# Wireless_Module_ESP32-H2_V1_0.net
KiCad netlist of a schematic drawn in EAGLE
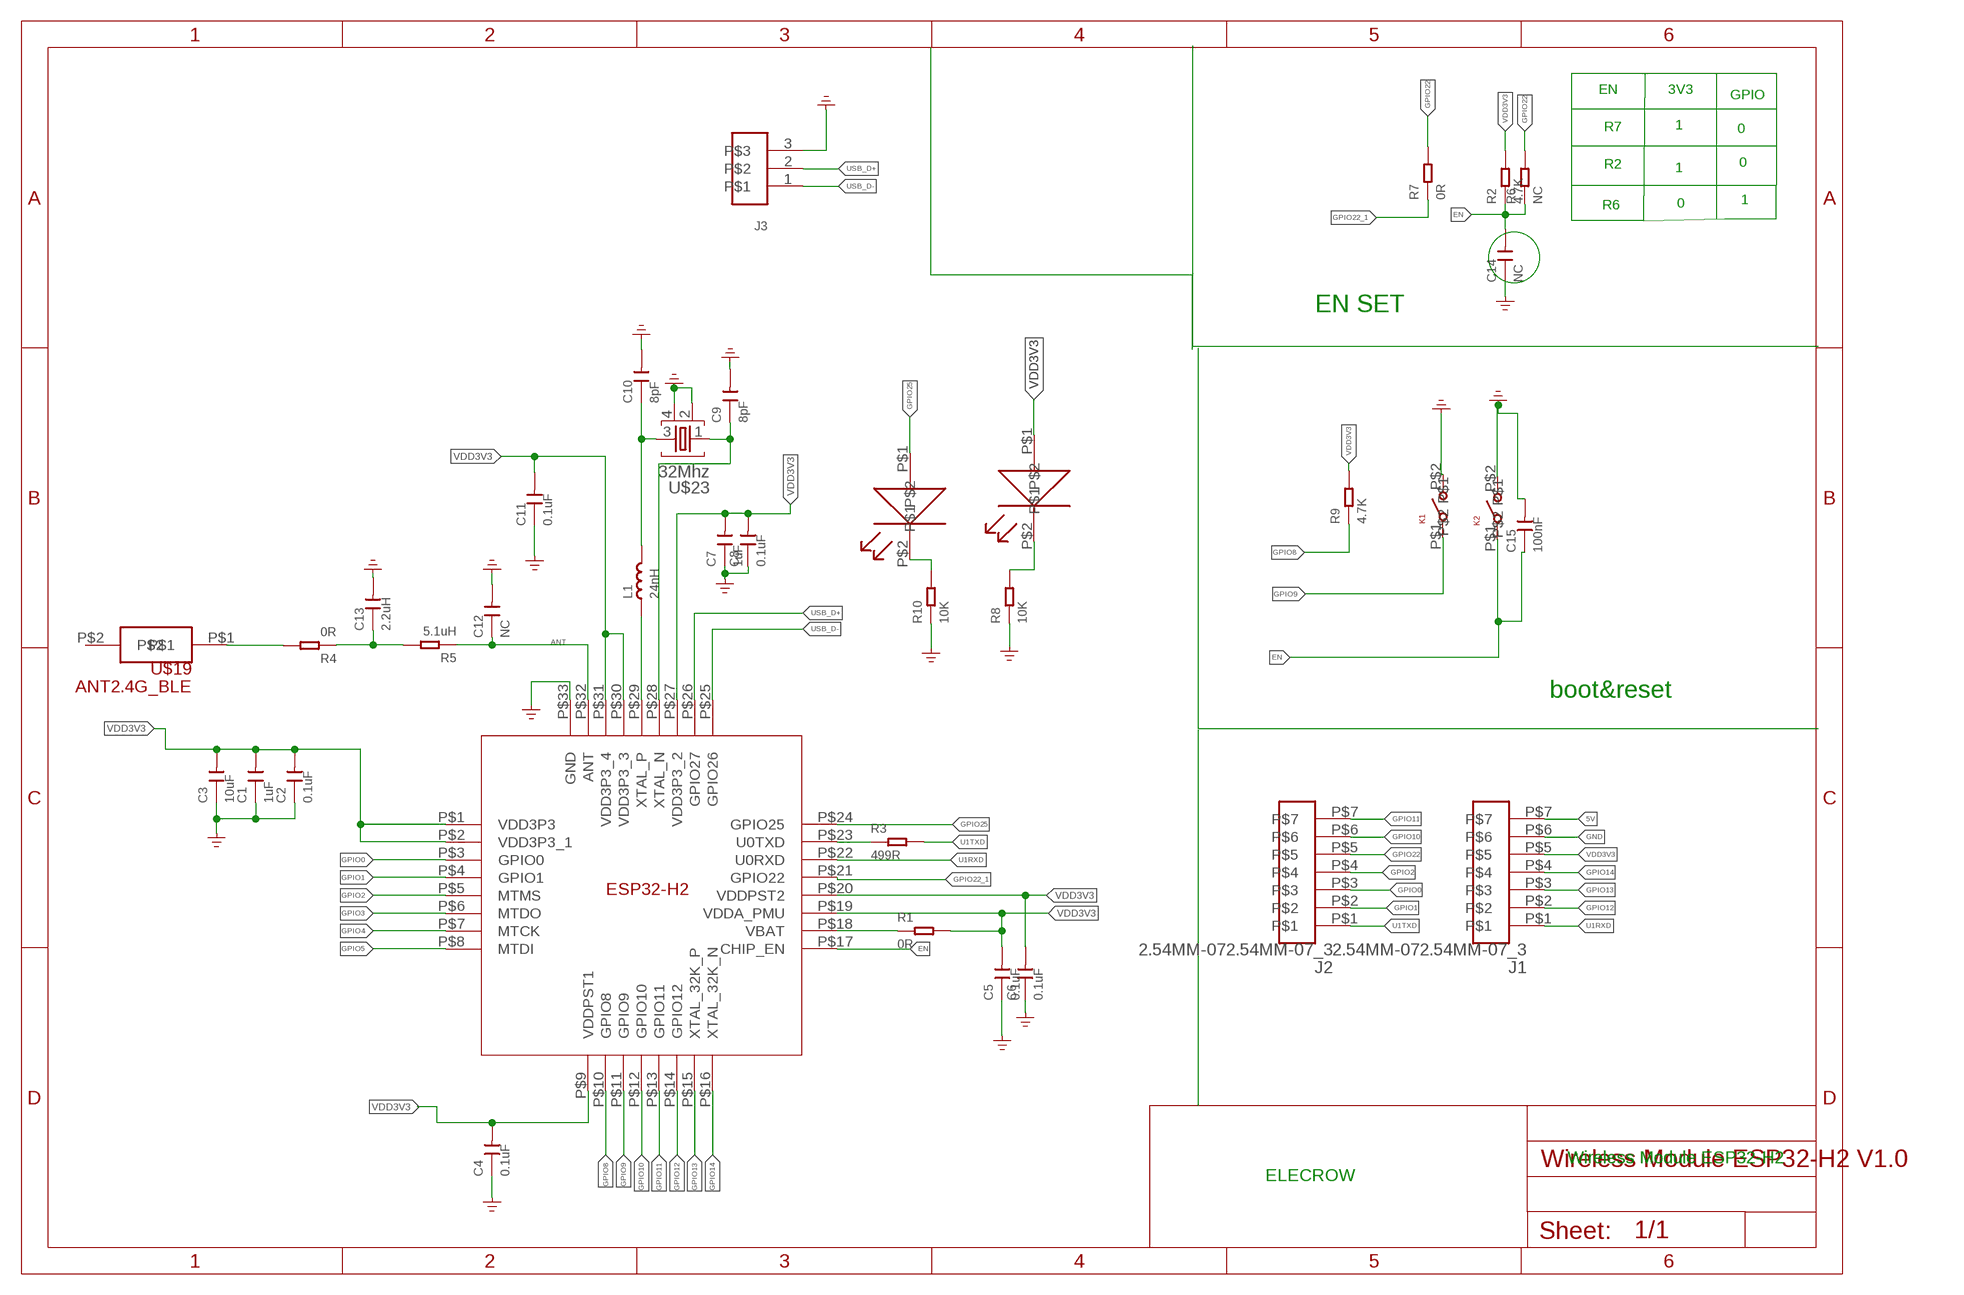
[diagram p0: schematic, sheet 1]

(export (version "E")
  (design (tool "Eeschema 10.0.6"))
  (components
    (comp (ref "C1")
      (value "1uF")
      (footprint "eagle-import:DISCRETE-NEW_C0402")
      (libsource (lib "eagle-import") (part "DISCRETE-NEW_CAP-0402"))
    )
    (comp (ref "C2")
      (value "0.1uF")
      (footprint "eagle-import:DISCRETE-NEW_C0402")
      (libsource (lib "eagle-import") (part "DISCRETE-NEW_CAP-0402"))
    )
    (comp (ref "C3")
      (value "10uF")
      (footprint "eagle-import:DISCRETE-NEW_C0402")
      (libsource (lib "eagle-import") (part "DISCRETE-NEW_CAP-0402"))
    )
    (comp (ref "C4")
      (value "0.1uF")
      (footprint "eagle-import:DISCRETE-NEW_C0402")
      (libsource (lib "eagle-import") (part "DISCRETE-NEW_CAP-0402"))
    )
    (comp (ref "C5")
      (value "0.1uF")
      (footprint "eagle-import:DISCRETE-NEW_C0402")
      (libsource (lib "eagle-import") (part "DISCRETE-NEW_CAP-0402"))
    )
    (comp (ref "C6")
      (value "0.1uF")
      (footprint "eagle-import:DISCRETE-NEW_C0402")
      (libsource (lib "eagle-import") (part "DISCRETE-NEW_CAP-0402"))
    )
    (comp (ref "C7")
      (value "1uF")
      (footprint "eagle-import:DISCRETE-NEW_C0402")
      (libsource (lib "eagle-import") (part "DISCRETE-NEW_CAP-0402"))
    )
    (comp (ref "C8")
      (value "0.1uF")
      (footprint "eagle-import:DISCRETE-NEW_C0402")
      (libsource (lib "eagle-import") (part "DISCRETE-NEW_CAP-0402"))
    )
    (comp (ref "C9")
      (value "8pF")
      (footprint "eagle-import:DISCRETE-NEW_C0402")
      (libsource (lib "eagle-import") (part "DISCRETE-NEW_CAP-0402"))
    )
    (comp (ref "C10")
      (value "8pF")
      (footprint "eagle-import:DISCRETE-NEW_C0402")
      (libsource (lib "eagle-import") (part "DISCRETE-NEW_CAP-0402"))
    )
    (comp (ref "C11")
      (value "0.1uF")
      (footprint "eagle-import:DISCRETE-NEW_C0402")
      (libsource (lib "eagle-import") (part "DISCRETE-NEW_CAP-0402"))
    )
    (comp (ref "C12")
      (value "NC")
      (footprint "eagle-import:DISCRETE-NEW_C0402")
      (libsource (lib "eagle-import") (part "DISCRETE-NEW_CAP-0402"))
    )
    (comp (ref "C13")
      (value "2.2uH")
      (footprint "eagle-import:DISCRETE-NEW_C0402")
      (libsource (lib "eagle-import") (part "DISCRETE-NEW_CAP-0402"))
    )
    (comp (ref "C14")
      (value "NC")
      (footprint "eagle-import:DISCRETE-NEW_C0402")
      (libsource (lib "eagle-import") (part "DISCRETE-NEW_CAP-0402"))
    )
    (comp (ref "C15")
      (value "100nF")
      (footprint "eagle-import:DISCRETE-NEW_C0402")
      (libsource (lib "eagle-import") (part "DISCRETE-NEW_CAP-0402"))
    )
    (comp (ref "J1")
      (value "2.54MM-072.54MM-07_3")
      (footprint "eagle-import:2.54MM-07_3")
      (libsource (lib "eagle-import") (part "2.54MM-072.54MM-07_3"))
    )
    (comp (ref "J2")
      (value "2.54MM-072.54MM-07_3")
      (footprint "eagle-import:2.54MM-07_3")
      (libsource (lib "eagle-import") (part "2.54MM-072.54MM-07_3"))
    )
    (comp (ref "J3")
      (value "1.27MM-3P")
      (footprint "eagle-import:1.27MM-3P")
      (libsource (lib "eagle-import") (part "1.27MM-3P"))
    )
    (comp (ref "K1")
      (value "KEY_SMD")
      (footprint "eagle-import:KEY_3_2.5")
      (libsource (lib "eagle-import") (part "KEY_SMD"))
    )
    (comp (ref "K2")
      (value "KEY_SMD")
      (footprint "eagle-import:KEY_3_2.5")
      (libsource (lib "eagle-import") (part "KEY_SMD"))
    )
    (comp (ref "L1")
      (value "24nH")
      (footprint "eagle-import:DISCRETE-NEW_L0402")
      (libsource (lib "eagle-import") (part "DISCRETE-NEW_INDUCTOR/FERRITE-BEAD0402"))
    )
    (comp (ref "LED1")
      (value "LED_SMT")
      (footprint "eagle-import:LED_0402")
      (libsource (lib "eagle-import") (part "LED_SMT"))
    )
    (comp (ref "LED2")
      (value "LED_SMT")
      (footprint "eagle-import:LED_0402")
      (libsource (lib "eagle-import") (part "LED_SMT"))
    )
    (comp (ref "R1")
      (value "0R")
      (footprint "eagle-import:DISCRETE-NEW_R0402")
      (libsource (lib "eagle-import") (part "DISCRETE-NEW_RES-0402"))
    )
    (comp (ref "R2")
      (value "4.7K")
      (footprint "eagle-import:DISCRETE-NEW_R0402")
      (libsource (lib "eagle-import") (part "DISCRETE-NEW_RES-0402"))
    )
    (comp (ref "R3")
      (value "499R")
      (footprint "eagle-import:DISCRETE-NEW_R0402")
      (libsource (lib "eagle-import") (part "DISCRETE-NEW_RES-0402"))
    )
    (comp (ref "R4")
      (value "0R")
      (footprint "eagle-import:DISCRETE-NEW_R0402")
      (libsource (lib "eagle-import") (part "DISCRETE-NEW_RES-0402"))
    )
    (comp (ref "R5")
      (value "5.1uH")
      (footprint "eagle-import:DISCRETE-NEW_R0402")
      (libsource (lib "eagle-import") (part "DISCRETE-NEW_RES-0402"))
    )
    (comp (ref "R6")
      (value "NC")
      (footprint "eagle-import:DISCRETE-NEW_R0402")
      (libsource (lib "eagle-import") (part "DISCRETE-NEW_RES-0402"))
    )
    (comp (ref "R7")
      (value "0R")
      (footprint "eagle-import:DISCRETE-NEW_R0402")
      (libsource (lib "eagle-import") (part "DISCRETE-NEW_RES-0402"))
    )
    (comp (ref "R8")
      (value "10K")
      (footprint "eagle-import:DISCRETE-NEW_R0402")
      (libsource (lib "eagle-import") (part "DISCRETE-NEW_RES-0402"))
    )
    (comp (ref "R9")
      (value "4.7K")
      (footprint "eagle-import:DISCRETE-NEW_R0402")
      (libsource (lib "eagle-import") (part "DISCRETE-NEW_RES-0402"))
    )
    (comp (ref "R10")
      (value "10K")
      (footprint "eagle-import:DISCRETE-NEW_R0402")
      (libsource (lib "eagle-import") (part "DISCRETE-NEW_RES-0402"))
    )
    (comp (ref "U$1")
      (value "ESP32-H2")
      (footprint "eagle-import:ESP32-H2")
      (libsource (lib "eagle-import") (part "ESP32-H2"))
    )
    (comp (ref "U$19")
      (value "ANT2.4G_BLE")
      (footprint "eagle-import:2.4G_BLE")
      (libsource (lib "eagle-import") (part "ANT2.4G_BLE"))
    )
    (comp (ref "U$23")
      (value "32Mhz")
      (footprint "eagle-import:NORDIC_NRF_BT-XTAL_2016_N")
      (libsource (lib "eagle-import") (part "NORDIC_NRF_XTAL_32MHZ"))
    )
  )
  (nets
    (net (code "1") (name "/ANT") (class "Default")
      (node (ref "C12") (pin "1") (pinfunction "1_1") (pintype "passive"))
      (node (ref "R5") (pin "1") (pinfunction "1_1") (pintype "passive"))
      (node (ref "U$1") (pin "P$32") (pinfunction "ANT_P$32") (pintype "bidirectional"))
    )
    (net (code "2") (name "5V") (class "Default")
      (node (ref "J1") (pin "P$7") (pinfunction "P$7_P$7") (pintype "bidirectional"))
    )
    (net (code "3") (name "EN") (class "Default")
      (node (ref "C14") (pin "2") (pinfunction "2_2") (pintype "passive"))
      (node (ref "C15") (pin "1") (pinfunction "1_1") (pintype "passive"))
      (node (ref "K2") (pin "P$1") (pinfunction "P$1_P$1") (pintype "bidirectional"))
      (node (ref "R2") (pin "1") (pinfunction "1_1") (pintype "passive"))
      (node (ref "R6") (pin "1") (pinfunction "1_1") (pintype "passive"))
      (node (ref "U$1") (pin "P$17") (pinfunction "CHIP_EN_P$17") (pintype "bidirectional"))
    )
    (net (code "4") (name "GND") (class "Default")
      (node (ref "C1") (pin "1") (pinfunction "1_1") (pintype "passive"))
      (node (ref "C10") (pin "2") (pinfunction "2_2") (pintype "passive"))
      (node (ref "C11") (pin "1") (pinfunction "1_1") (pintype "passive"))
      (node (ref "C12") (pin "2") (pinfunction "2_2") (pintype "passive"))
      (node (ref "C13") (pin "2") (pinfunction "2_2") (pintype "passive"))
      (node (ref "C14") (pin "1") (pinfunction "1_1") (pintype "passive"))
      (node (ref "C15") (pin "2") (pinfunction "2_2") (pintype "passive"))
      (node (ref "C2") (pin "1") (pinfunction "1_1") (pintype "passive"))
      (node (ref "C3") (pin "1") (pinfunction "1_1") (pintype "passive"))
      (node (ref "C4") (pin "1") (pinfunction "1_1") (pintype "passive"))
      (node (ref "C5") (pin "1") (pinfunction "1_1") (pintype "passive"))
      (node (ref "C6") (pin "1") (pinfunction "1_1") (pintype "passive"))
      (node (ref "C7") (pin "1") (pinfunction "1_1") (pintype "passive"))
      (node (ref "C8") (pin "1") (pinfunction "1_1") (pintype "passive"))
      (node (ref "C9") (pin "2") (pinfunction "2_2") (pintype "passive"))
      (node (ref "J1") (pin "P$6") (pinfunction "P$6_P$6") (pintype "bidirectional"))
      (node (ref "J3") (pin "3") (pinfunction "P$3_3") (pintype "bidirectional"))
      (node (ref "K1") (pin "P$2") (pinfunction "P$2_P$2") (pintype "bidirectional"))
      (node (ref "K2") (pin "P$2") (pinfunction "P$2_P$2") (pintype "bidirectional"))
      (node (ref "R10") (pin "1") (pinfunction "1_1") (pintype "passive"))
      (node (ref "R8") (pin "1") (pinfunction "1_1") (pintype "passive"))
      (node (ref "U$1") (pin "P$33") (pinfunction "GND_P$33") (pintype "power_in"))
      (node (ref "U$23") (pin "2") (pinfunction "2_2") (pintype "passive"))
      (node (ref "U$23") (pin "4") (pinfunction "4_4") (pintype "passive"))
    )
    (net (code "5") (name "GPIO0") (class "Default")
      (node (ref "J2") (pin "P$3") (pinfunction "P$3_P$3") (pintype "bidirectional"))
      (node (ref "U$1") (pin "P$3") (pinfunction "GPIO0_P$3") (pintype "bidirectional"))
    )
    (net (code "6") (name "GPIO1") (class "Default")
      (node (ref "J2") (pin "P$2") (pinfunction "P$2_P$2") (pintype "bidirectional"))
      (node (ref "U$1") (pin "P$4") (pinfunction "GPIO1_P$4") (pintype "bidirectional"))
    )
    (net (code "7") (name "GPIO2") (class "Default")
      (node (ref "J2") (pin "P$4") (pinfunction "P$4_P$4") (pintype "bidirectional"))
      (node (ref "U$1") (pin "P$5") (pinfunction "MTMS_P$5") (pintype "bidirectional"))
    )
    (net (code "8") (name "GPIO3") (class "Default")
      (node (ref "U$1") (pin "P$6") (pinfunction "MTDO_P$6") (pintype "bidirectional"))
    )
    (net (code "9") (name "GPIO4") (class "Default")
      (node (ref "U$1") (pin "P$7") (pinfunction "MTCK_P$7") (pintype "bidirectional"))
    )
    (net (code "10") (name "GPIO5") (class "Default")
      (node (ref "U$1") (pin "P$8") (pinfunction "MTDI_P$8") (pintype "bidirectional"))
    )
    (net (code "11") (name "GPIO8") (class "Default")
      (node (ref "R9") (pin "1") (pinfunction "1_1") (pintype "passive"))
      (node (ref "U$1") (pin "P$10") (pinfunction "GPIO8_P$10") (pintype "bidirectional"))
    )
    (net (code "12") (name "GPIO9") (class "Default")
      (node (ref "K1") (pin "P$1") (pinfunction "P$1_P$1") (pintype "bidirectional"))
      (node (ref "U$1") (pin "P$11") (pinfunction "GPIO9_P$11") (pintype "bidirectional"))
    )
    (net (code "13") (name "GPIO10") (class "Default")
      (node (ref "J2") (pin "P$6") (pinfunction "P$6_P$6") (pintype "bidirectional"))
      (node (ref "U$1") (pin "P$12") (pinfunction "GPIO10_P$12") (pintype "bidirectional"))
    )
    (net (code "14") (name "GPIO11") (class "Default")
      (node (ref "J2") (pin "P$7") (pinfunction "P$7_P$7") (pintype "bidirectional"))
      (node (ref "U$1") (pin "P$13") (pinfunction "GPIO11_P$13") (pintype "bidirectional"))
    )
    (net (code "15") (name "GPIO12") (class "Default")
      (node (ref "J1") (pin "P$2") (pinfunction "P$2_P$2") (pintype "bidirectional"))
      (node (ref "U$1") (pin "P$14") (pinfunction "GPIO12_P$14") (pintype "bidirectional"))
    )
    (net (code "16") (name "GPIO13") (class "Default")
      (node (ref "J1") (pin "P$3") (pinfunction "P$3_P$3") (pintype "bidirectional"))
      (node (ref "U$1") (pin "P$15") (pinfunction "XTAL_32K_P_P$15") (pintype "bidirectional"))
    )
    (net (code "17") (name "GPIO14") (class "Default")
      (node (ref "J1") (pin "P$4") (pinfunction "P$4_P$4") (pintype "bidirectional"))
      (node (ref "U$1") (pin "P$16") (pinfunction "XTAL_32K_N_P$16") (pintype "bidirectional"))
    )
    (net (code "18") (name "GPIO22") (class "Default")
      (node (ref "J2") (pin "P$5") (pinfunction "P$5_P$5") (pintype "bidirectional"))
      (node (ref "R6") (pin "2") (pinfunction "2_2") (pintype "passive"))
      (node (ref "R7") (pin "2") (pinfunction "2_2") (pintype "passive"))
    )
    (net (code "19") (name "GPIO22_1") (class "Default")
      (node (ref "R7") (pin "1") (pinfunction "1_1") (pintype "passive"))
      (node (ref "U$1") (pin "P$21") (pinfunction "GPIO22_P$21") (pintype "bidirectional"))
    )
    (net (code "20") (name "GPIO25") (class "Default")
      (node (ref "LED1") (pin "P$1") (pinfunction "P$1_P$1") (pintype "bidirectional"))
      (node (ref "U$1") (pin "P$24") (pinfunction "GPIO25_P$24") (pintype "bidirectional"))
    )
    (net (code "21") (name "Net-(C10-Pad1)") (class "Default")
      (node (ref "C10") (pin "1") (pinfunction "1_1") (pintype "passive"))
      (node (ref "L1") (pin "2") (pinfunction "2_2") (pintype "passive"))
      (node (ref "U$23") (pin "3") (pinfunction "3_3") (pintype "passive"))
    )
    (net (code "22") (name "Net-(C13-Pad1)") (class "Default")
      (node (ref "C13") (pin "1") (pinfunction "1_1") (pintype "passive"))
      (node (ref "R4") (pin "1") (pinfunction "1_1") (pintype "passive"))
      (node (ref "R5") (pin "2") (pinfunction "2_2") (pintype "passive"))
    )
    (net (code "23") (name "Net-(LED1-PadP$2)") (class "Default")
      (node (ref "LED1") (pin "P$2") (pinfunction "P$2_P$2") (pintype "bidirectional"))
      (node (ref "R10") (pin "2") (pinfunction "2_2") (pintype "passive"))
    )
    (net (code "24") (name "Net-(LED2-PadP$2)") (class "Default")
      (node (ref "LED2") (pin "P$2") (pinfunction "P$2_P$2") (pintype "bidirectional"))
      (node (ref "R8") (pin "2") (pinfunction "2_2") (pintype "passive"))
    )
    (net (code "25") (name "Net-(R4-Pad2)") (class "Default")
      (node (ref "R4") (pin "2") (pinfunction "2_2") (pintype "passive"))
      (node (ref "U$19") (pin "P$1") (pinfunction "P$1_P$1") (pintype "bidirectional"))
    )
    (net (code "26") (name "Net-(U$1-U0TXD)") (class "Default")
      (node (ref "R3") (pin "1") (pinfunction "1_1") (pintype "passive"))
      (node (ref "U$1") (pin "P$23") (pinfunction "U0TXD_P$23") (pintype "bidirectional"))
    )
    (net (code "27") (name "Net-(U$1-VBAT)") (class "Default")
      (node (ref "R1") (pin "1") (pinfunction "1_1") (pintype "passive"))
      (node (ref "U$1") (pin "P$18") (pinfunction "VBAT_P$18") (pintype "bidirectional"))
    )
    (net (code "28") (name "Net-(U$1-XTAL_N)") (class "Default")
      (node (ref "C9") (pin "1") (pinfunction "1_1") (pintype "passive"))
      (node (ref "U$1") (pin "P$28") (pinfunction "XTAL_N_P$28") (pintype "bidirectional"))
      (node (ref "U$23") (pin "1") (pinfunction "1_1") (pintype "passive"))
    )
    (net (code "29") (name "Net-(U$1-XTAL_P)") (class "Default")
      (node (ref "L1") (pin "1") (pinfunction "1_1") (pintype "passive"))
      (node (ref "U$1") (pin "P$29") (pinfunction "XTAL_P_P$29") (pintype "bidirectional"))
    )
    (net (code "30") (name "U1RXD") (class "Default")
      (node (ref "J1") (pin "P$1") (pinfunction "P$1_P$1") (pintype "bidirectional"))
      (node (ref "U$1") (pin "P$22") (pinfunction "U0RXD_P$22") (pintype "bidirectional"))
    )
    (net (code "31") (name "U1TXD") (class "Default")
      (node (ref "J2") (pin "P$1") (pinfunction "P$1_P$1") (pintype "bidirectional"))
      (node (ref "R3") (pin "2") (pinfunction "2_2") (pintype "passive"))
    )
    (net (code "32") (name "USB_D+") (class "Default")
      (node (ref "J3") (pin "2") (pinfunction "P$2_2") (pintype "bidirectional"))
      (node (ref "U$1") (pin "P$26") (pinfunction "GPIO27_P$26") (pintype "bidirectional"))
    )
    (net (code "33") (name "USB_D-") (class "Default")
      (node (ref "J3") (pin "1") (pinfunction "P$1_1") (pintype "bidirectional"))
      (node (ref "U$1") (pin "P$25") (pinfunction "GPIO26_P$25") (pintype "bidirectional"))
    )
    (net (code "34") (name "VDD3V3") (class "Default")
      (node (ref "C1") (pin "2") (pinfunction "2_2") (pintype "passive"))
      (node (ref "C11") (pin "2") (pinfunction "2_2") (pintype "passive"))
      (node (ref "C2") (pin "2") (pinfunction "2_2") (pintype "passive"))
      (node (ref "C3") (pin "2") (pinfunction "2_2") (pintype "passive"))
      (node (ref "C4") (pin "2") (pinfunction "2_2") (pintype "passive"))
      (node (ref "C5") (pin "2") (pinfunction "2_2") (pintype "passive"))
      (node (ref "C6") (pin "2") (pinfunction "2_2") (pintype "passive"))
      (node (ref "C7") (pin "2") (pinfunction "2_2") (pintype "passive"))
      (node (ref "C8") (pin "2") (pinfunction "2_2") (pintype "passive"))
      (node (ref "J1") (pin "P$5") (pinfunction "P$5_P$5") (pintype "bidirectional"))
      (node (ref "LED2") (pin "P$1") (pinfunction "P$1_P$1") (pintype "bidirectional"))
      (node (ref "R1") (pin "2") (pinfunction "2_2") (pintype "passive"))
      (node (ref "R2") (pin "2") (pinfunction "2_2") (pintype "passive"))
      (node (ref "R9") (pin "2") (pinfunction "2_2") (pintype "passive"))
      (node (ref "U$1") (pin "P$1") (pinfunction "VDD3P3_P$1") (pintype "power_in"))
      (node (ref "U$1") (pin "P$19") (pinfunction "VDDA_PMU_P$19") (pintype "bidirectional"))
      (node (ref "U$1") (pin "P$2") (pinfunction "VDD3P3_1_P$2") (pintype "power_in"))
      (node (ref "U$1") (pin "P$20") (pinfunction "VDDPST2_P$20") (pintype "bidirectional"))
      (node (ref "U$1") (pin "P$27") (pinfunction "VDD3P3_2_P$27") (pintype "power_in"))
      (node (ref "U$1") (pin "P$30") (pinfunction "VDD3P3_3_P$30") (pintype "power_in"))
      (node (ref "U$1") (pin "P$31") (pinfunction "VDD3P3_4_P$31") (pintype "power_in"))
      (node (ref "U$1") (pin "P$9") (pinfunction "VDDPST1_P$9") (pintype "bidirectional"))
    )
    (net (code "35") (name "unconnected-(U$19-PadP$2)") (class "Default")
      (node (ref "U$19") (pin "P$2") (pinfunction "P$2_P$2") (pintype "bidirectional"))
    )
  )
)
